# HW_HDSP2072.net
KiCad netlist of a schematic drawn in Altium Designer
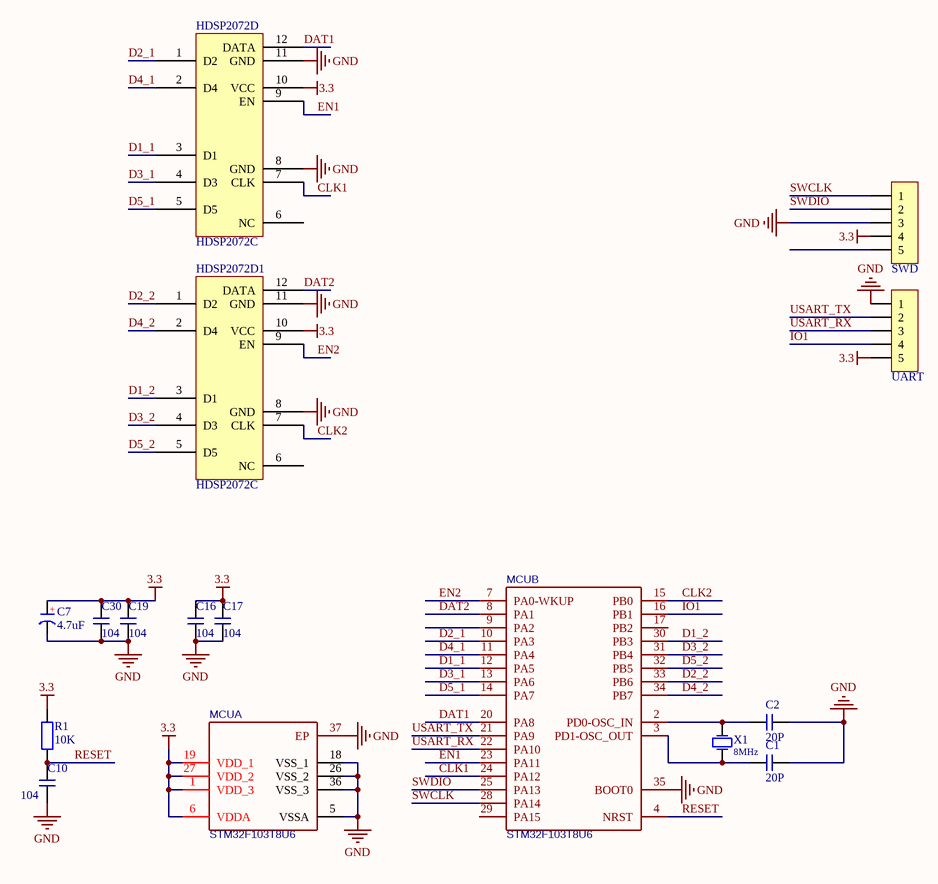
[diagram p0: HW_HDSP2072.SchDoc]

(export (version "E")
  (design (tool "Eeschema 10.0.6"))
  (components
    (comp (ref "C1") (value "20P") (footprint "0603C") (libsource (lib "Schlib1") (part "电容")))
    (comp (ref "C2") (value "20P") (footprint "0603C") (libsource (lib "Schlib1") (part "电容")))
    (comp (ref "C7")
      (value "4.7uF")
      (footprint "3528-B-TA")
      (description "贴片钽电容")
      (fields (field (name "版权归属") "源创客"))
      (libsource (lib "3.1   - 电阻-电容-电感") (part "C-CD"))
    )
    (comp (ref "C10") (value "104") (footprint "0603C") (libsource (lib "Schlib1") (part "电容")))
    (comp (ref "C16") (value "104") (footprint "0603C") (libsource (lib "Schlib1") (part "电容")))
    (comp (ref "C17") (value "104") (footprint "0603C") (libsource (lib "Schlib1") (part "电容")))
    (comp (ref "C19") (value "104") (footprint "0603C") (libsource (lib "Schlib1") (part "电容")))
    (comp (ref "C30") (value "104") (footprint "0603C") (libsource (lib "Schlib1") (part "电容")))
    (comp (ref "HDSP2072D")
      (value "HDSP2072C")
      (footprint "HDSP2072SH")
      (libsource (lib "HDSP2072") (part "HDSP2072"))
    )
    (comp (ref "HDSP2072D1")
      (value "HDSP2072C")
      (footprint "HDSP2072SH")
      (libsource (lib "HDSP2072") (part "HDSP2072"))
    )
    (comp (ref "MCU")
      (value "STM32F103T8U6")
      (footprint "VFQFPN36_L6.0-W6.0-P0.50-BL-EP3.7")
      (fields (field (name "BOM_SUPPLIER PART") "C19671") (field (name "SUBPART_NO") "2"))
      (libsource (lib "HDSP2072") (part "STM32F103T8U6"))
    )
    (comp (ref "R1")
      (value "10K")
      (footprint "0603R")
      (description "贴片电阻")
      (fields (field (name "版权归属") "源创客"))
      (libsource (lib "3.1   - 电阻-电容-电感") (part "R"))
    )
    (comp (ref "SWD")
      (value "HDR-1X5")
      (footprint "HDR2.54-LI-5P")
      (description "5P接插件")
      (fields (field (name "版权归属") "源创客"))
      (libsource (lib "4.5   - 接插件-脚距2.54") (part "Header 5"))
    )
    (comp (ref "UART")
      (value "HDR-1X5")
      (footprint "HDR2.54-LI-5P")
      (description "5P接插件")
      (fields (field (name "版权归属") "源创客"))
      (libsource (lib "4.5   - 接插件-脚距2.54") (part "Header 5"))
    )
    (comp (ref "X1")
      (value "8MHz")
      (footprint "OSC 5032-2P")
      (description "XTAL,8MHz,±20PPM,12.6*4.5")
      (fields (field (name "Comment") "1.6.1.01.005.001"))
      (libsource (lib "Mark_7") (part "1.6.1.01.005.001"))
    )
  )
  (nets
    (net (code "1") (name "/CLK1") (class "Default")
      (node (ref "HDSP2072D") (pin "7") (pinfunction "CLK_7") (pintype "passive"))
      (node (ref "MCU") (pin "24") (pinfunction "PA12_24") (pintype "passive"))
    )
    (net (code "2") (name "/CLK2") (class "Default")
      (node (ref "HDSP2072D1") (pin "7") (pinfunction "CLK_7") (pintype "passive"))
      (node (ref "MCU") (pin "15") (pinfunction "PB0_15") (pintype "passive"))
    )
    (net (code "3") (name "/D1_1") (class "Default")
      (node (ref "HDSP2072D") (pin "3") (pinfunction "D1_3") (pintype "passive"))
      (node (ref "MCU") (pin "12") (pinfunction "PA5_12") (pintype "passive"))
    )
    (net (code "4") (name "/D1_2") (class "Default")
      (node (ref "HDSP2072D1") (pin "3") (pinfunction "D1_3") (pintype "passive"))
      (node (ref "MCU") (pin "30") (pinfunction "PB3_30") (pintype "passive"))
    )
    (net (code "5") (name "/D2_1") (class "Default")
      (node (ref "HDSP2072D") (pin "1") (pinfunction "D2_1") (pintype "passive"))
      (node (ref "MCU") (pin "10") (pinfunction "PA3_10") (pintype "passive"))
    )
    (net (code "6") (name "/D2_2") (class "Default")
      (node (ref "HDSP2072D1") (pin "1") (pinfunction "D2_1") (pintype "passive"))
      (node (ref "MCU") (pin "33") (pinfunction "PB6_33") (pintype "passive"))
    )
    (net (code "7") (name "/D3_1") (class "Default")
      (node (ref "HDSP2072D") (pin "4") (pinfunction "D3_4") (pintype "passive"))
      (node (ref "MCU") (pin "13") (pinfunction "PA6_13") (pintype "passive"))
    )
    (net (code "8") (name "/D3_2") (class "Default")
      (node (ref "HDSP2072D1") (pin "4") (pinfunction "D3_4") (pintype "passive"))
      (node (ref "MCU") (pin "31") (pinfunction "PB4_31") (pintype "passive"))
    )
    (net (code "9") (name "/D4_1") (class "Default")
      (node (ref "HDSP2072D") (pin "2") (pinfunction "D4_2") (pintype "passive"))
      (node (ref "MCU") (pin "11") (pinfunction "PA4_11") (pintype "passive"))
    )
    (net (code "10") (name "/D4_2") (class "Default")
      (node (ref "HDSP2072D1") (pin "2") (pinfunction "D4_2") (pintype "passive"))
      (node (ref "MCU") (pin "34") (pinfunction "PB7_34") (pintype "passive"))
    )
    (net (code "11") (name "/D5_1") (class "Default")
      (node (ref "HDSP2072D") (pin "5") (pinfunction "D5_5") (pintype "passive"))
      (node (ref "MCU") (pin "14") (pinfunction "PA7_14") (pintype "passive"))
    )
    (net (code "12") (name "/D5_2") (class "Default")
      (node (ref "HDSP2072D1") (pin "5") (pinfunction "D5_5") (pintype "passive"))
      (node (ref "MCU") (pin "32") (pinfunction "PB5_32") (pintype "passive"))
    )
    (net (code "13") (name "/DAT1") (class "Default")
      (node (ref "HDSP2072D") (pin "12") (pinfunction "DATA_12") (pintype "passive"))
      (node (ref "MCU") (pin "20") (pinfunction "PA8_20") (pintype "passive"))
    )
    (net (code "14") (name "/DAT2") (class "Default")
      (node (ref "HDSP2072D1") (pin "12") (pinfunction "DATA_12") (pintype "passive"))
      (node (ref "MCU") (pin "8") (pinfunction "PA1_8") (pintype "passive"))
    )
    (net (code "15") (name "/EN1") (class "Default")
      (node (ref "HDSP2072D") (pin "9") (pinfunction "EN_9") (pintype "passive"))
      (node (ref "MCU") (pin "23") (pinfunction "PA11_23") (pintype "passive"))
    )
    (net (code "16") (name "/EN2") (class "Default")
      (node (ref "HDSP2072D1") (pin "9") (pinfunction "EN_9") (pintype "passive"))
      (node (ref "MCU") (pin "7") (pinfunction "PA0-WKUP_7") (pintype "passive"))
    )
    (net (code "17") (name "/IO1") (class "Default")
      (node (ref "MCU") (pin "16") (pinfunction "PB1_16") (pintype "passive"))
      (node (ref "UART") (pin "4") (pinfunction "4_4") (pintype "passive"))
    )
    (net (code "18") (name "/RESET") (class "Default")
      (node (ref "C10") (pin "1") (pinfunction "1_1") (pintype "passive"))
      (node (ref "MCU") (pin "4") (pinfunction "NRST_4") (pintype "passive"))
      (node (ref "R1") (pin "2") (pinfunction "2_2") (pintype "passive"))
    )
    (net (code "19") (name "/SWCLK") (class "Default")
      (node (ref "MCU") (pin "28") (pinfunction "PA14_28") (pintype "passive"))
      (node (ref "SWD") (pin "1") (pinfunction "1_1") (pintype "passive"))
    )
    (net (code "20") (name "/SWDIO") (class "Default")
      (node (ref "MCU") (pin "25") (pinfunction "PA13_25") (pintype "passive"))
      (node (ref "SWD") (pin "2") (pinfunction "2_2") (pintype "passive"))
    )
    (net (code "21") (name "/USART_RX") (class "Default")
      (node (ref "MCU") (pin "22") (pinfunction "PA10_22") (pintype "passive"))
      (node (ref "UART") (pin "3") (pinfunction "3_3") (pintype "passive"))
    )
    (net (code "22") (name "/USART_TX") (class "Default")
      (node (ref "MCU") (pin "21") (pinfunction "PA9_21") (pintype "passive"))
      (node (ref "UART") (pin "2") (pinfunction "2_2") (pintype "passive"))
    )
    (net (code "23") (name "3.3") (class "Default")
      (node (ref "C16") (pin "1") (pinfunction "1_1") (pintype "passive"))
      (node (ref "C17") (pin "1") (pinfunction "1_1") (pintype "passive"))
      (node (ref "C19") (pin "1") (pinfunction "1_1") (pintype "passive"))
      (node (ref "C30") (pin "1") (pinfunction "1_1") (pintype "passive"))
      (node (ref "C7") (pin "1") (pinfunction "A_1") (pintype "passive"))
      (node (ref "HDSP2072D") (pin "10") (pinfunction "VCC_10") (pintype "passive"))
      (node (ref "HDSP2072D1") (pin "10") (pinfunction "VCC_10") (pintype "passive"))
      (node (ref "MCU") (pin "1") (pinfunction "VDD_3_1") (pintype "passive"))
      (node (ref "MCU") (pin "19") (pinfunction "VDD_1_19") (pintype "passive"))
      (node (ref "MCU") (pin "27") (pinfunction "VDD_2_27") (pintype "passive"))
      (node (ref "MCU") (pin "6") (pinfunction "VDDA_6") (pintype "passive"))
      (node (ref "R1") (pin "1") (pinfunction "1_1") (pintype "passive"))
      (node (ref "SWD") (pin "4") (pinfunction "4_4") (pintype "passive"))
      (node (ref "UART") (pin "5") (pinfunction "5_5") (pintype "passive"))
    )
    (net (code "24") (name "GND") (class "Default")
      (node (ref "C1") (pin "1") (pinfunction "1_1") (pintype "passive"))
      (node (ref "C10") (pin "2") (pinfunction "2_2") (pintype "passive"))
      (node (ref "C16") (pin "2") (pinfunction "2_2") (pintype "passive"))
      (node (ref "C17") (pin "2") (pinfunction "2_2") (pintype "passive"))
      (node (ref "C19") (pin "2") (pinfunction "2_2") (pintype "passive"))
      (node (ref "C2") (pin "1") (pinfunction "1_1") (pintype "passive"))
      (node (ref "C30") (pin "2") (pinfunction "2_2") (pintype "passive"))
      (node (ref "C7") (pin "2") (pinfunction "K_2") (pintype "passive"))
      (node (ref "HDSP2072D") (pin "11") (pinfunction "GND_11") (pintype "passive"))
      (node (ref "HDSP2072D") (pin "8") (pinfunction "GND_8") (pintype "passive"))
      (node (ref "HDSP2072D1") (pin "11") (pinfunction "GND_11") (pintype "passive"))
      (node (ref "HDSP2072D1") (pin "8") (pinfunction "GND_8") (pintype "passive"))
      (node (ref "MCU") (pin "18") (pinfunction "VSS_1_18") (pintype "passive"))
      (node (ref "MCU") (pin "26") (pinfunction "VSS_2_26") (pintype "passive"))
      (node (ref "MCU") (pin "35") (pinfunction "BOOT0_35") (pintype "passive"))
      (node (ref "MCU") (pin "36") (pinfunction "VSS_3_36") (pintype "passive"))
      (node (ref "MCU") (pin "37") (pinfunction "EP_37") (pintype "passive"))
      (node (ref "MCU") (pin "5") (pinfunction "VSSA_5") (pintype "passive"))
      (node (ref "SWD") (pin "3") (pinfunction "3_3") (pintype "passive"))
      (node (ref "UART") (pin "1") (pinfunction "1_1") (pintype "passive"))
    )
    (net (code "25") (name "Net-(MCUB-PD0-OSC_IN)") (class "Default")
      (node (ref "C2") (pin "2") (pinfunction "2_2") (pintype "passive"))
      (node (ref "MCU") (pin "2") (pinfunction "PD0-OSC_IN_2") (pintype "passive"))
      (node (ref "X1") (pin "1") (pinfunction "OSC1_1") (pintype "passive"))
    )
    (net (code "26") (name "Net-(MCUB-PD1-OSC_OUT)") (class "Default")
      (node (ref "C1") (pin "2") (pinfunction "2_2") (pintype "passive"))
      (node (ref "MCU") (pin "3") (pinfunction "PD1-OSC_OUT_3") (pintype "passive"))
      (node (ref "X1") (pin "2") (pinfunction "OSC2_2") (pintype "passive"))
    )
    (net (code "27") (name "unconnected-(HDSP2072D-NC-Pad6)") (class "Default")
      (node (ref "HDSP2072D") (pin "6") (pinfunction "NC_6") (pintype "passive"))
    )
    (net (code "28") (name "unconnected-(HDSP2072D1-NC-Pad6)") (class "Default")
      (node (ref "HDSP2072D1") (pin "6") (pinfunction "NC_6") (pintype "passive"))
    )
    (net (code "29") (name "unconnected-(MCUB-PA2-Pad9)") (class "Default")
      (node (ref "MCU") (pin "9") (pinfunction "PA2_9") (pintype "passive"))
    )
    (net (code "30") (name "unconnected-(MCUB-PA15-Pad29)") (class "Default")
      (node (ref "MCU") (pin "29") (pinfunction "PA15_29") (pintype "passive"))
    )
    (net (code "31") (name "unconnected-(MCUB-PB2-Pad17)") (class "Default")
      (node (ref "MCU") (pin "17") (pinfunction "PB2_17") (pintype "passive"))
    )
    (net (code "32") (name "unconnected-(SWD-Pad5)") (class "Default")
      (node (ref "SWD") (pin "5") (pinfunction "5_5") (pintype "passive"))
    )
  )
)
